# Sunfish_ECU_CPU_RevA.net
KiCad netlist of a schematic drawn in Altium Designer
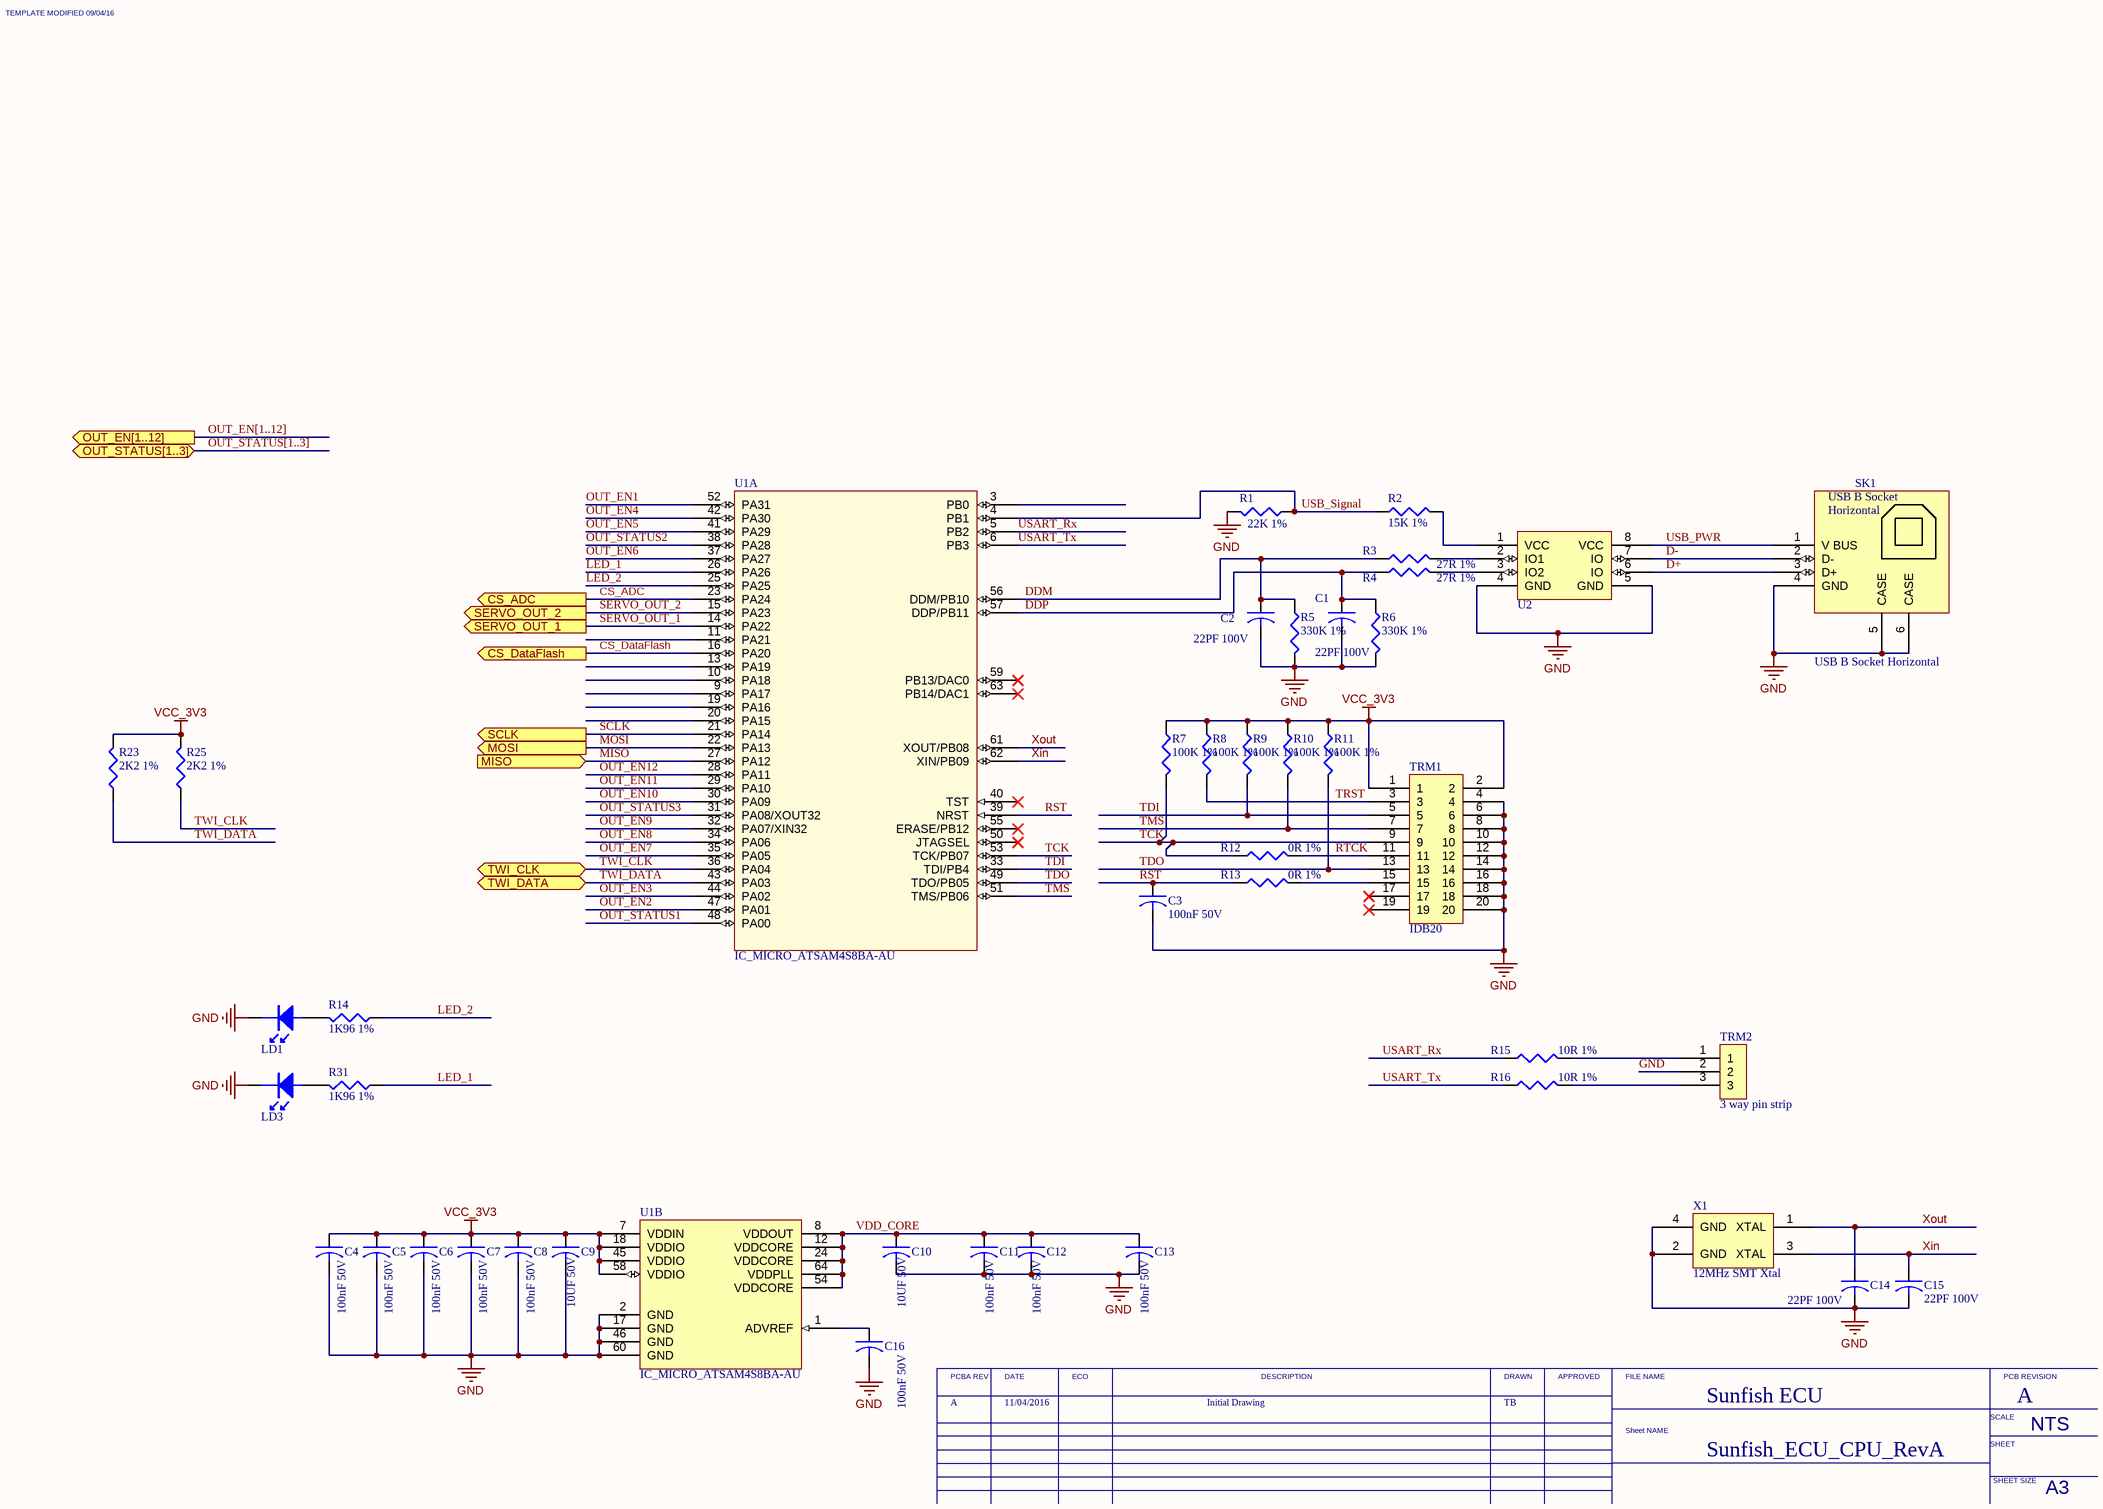
[diagram p0: Sunfish_ECU_CPU_RevA.SchDoc]

(export (version "E")
  (design (tool "Eeschema 10.0.6"))
  (components
    (comp (ref "C1")
      (value "22PF 100V")
      (footprint "0603")
      (description "CAP CER 22PF 100V 5% NP0 0603")
      (fields (field (name "MANUFACTURER") "Murata"))
      (libsource (lib "") (part "CAP_22PF_100V_5%_0603_1"))
    )
    (comp (ref "C2")
      (value "22PF 100V")
      (footprint "0603")
      (description "CAP CER 22PF 100V 5% NP0 0603")
      (fields (field (name "MANUFACTURER") "Murata"))
      (libsource (lib "") (part "CAP_22PF_100V_5%_0603_1"))
    )
    (comp (ref "C3")
      (value "100nF 50V")
      (footprint "0603")
      (description "CAP CER 100nF 50V 10% X7R 0603")
      (fields (field (name "MANUFACTURER") "Murata"))
      (libsource (lib "ThrusterControl") (part "CAP_100NF_50V_10%_0603"))
    )
    (comp (ref "C4")
      (value "100nF 50V")
      (footprint "0603")
      (description "CAP CER 100nF 50V 10% X7R 0603")
      (fields (field (name "MANUFACTURER") "Murata"))
      (libsource (lib "Caps") (part "CAP_100NF_50V_10%_0603"))
    )
    (comp (ref "C5")
      (value "100nF 50V")
      (footprint "0603")
      (description "CAP CER 100nF 50V 10% X7R 0603")
      (fields (field (name "MANUFACTURER") "Murata"))
      (libsource (lib "Caps") (part "CAP_100NF_50V_10%_0603"))
    )
    (comp (ref "C6")
      (value "100nF 50V")
      (footprint "0603")
      (description "CAP CER 100nF 50V 10% X7R 0603")
      (fields (field (name "MANUFACTURER") "Murata"))
      (libsource (lib "Caps") (part "CAP_100NF_50V_10%_0603"))
    )
    (comp (ref "C7")
      (value "100nF 50V")
      (footprint "0603")
      (description "CAP CER 100nF 50V 10% X7R 0603")
      (fields (field (name "MANUFACTURER") "Murata"))
      (libsource (lib "Caps") (part "CAP_100NF_50V_10%_0603"))
    )
    (comp (ref "C8")
      (value "100nF 50V")
      (footprint "0603")
      (description "CAP CER 100nF 50V 10% X7R 0603")
      (fields (field (name "MANUFACTURER") "Murata"))
      (libsource (lib "Caps") (part "CAP_100NF_50V_10%_0603"))
    )
    (comp (ref "C9")
      (value "10UF 50V")
      (footprint "1206")
      (description "CAP CER 10UF 50V 10% X5R 1206")
      (fields (field (name "MANUFACTURER") "Murata"))
      (libsource (lib "ThrusterControl") (part "CAP_10UF_50V_10%_1206"))
    )
    (comp (ref "C10")
      (value "10UF 50V")
      (footprint "1206")
      (description "CAP CER 10UF 50V 10% X5R 1206")
      (fields (field (name "MANUFACTURER") "Murata"))
      (libsource (lib "ThrusterControl") (part "CAP_10UF_50V_10%_1206"))
    )
    (comp (ref "C11")
      (value "100nF 50V")
      (footprint "0603")
      (description "CAP CER 100nF 50V 10% X7R 0603")
      (fields (field (name "MANUFACTURER") "Murata"))
      (libsource (lib "") (part "CAP_100NF_50V_10%_0603_1"))
    )
    (comp (ref "C12")
      (value "100nF 50V")
      (footprint "0603")
      (description "CAP CER 100nF 50V 10% X7R 0603")
      (fields (field (name "MANUFACTURER") "Murata"))
      (libsource (lib "") (part "CAP_100NF_50V_10%_0603_1"))
    )
    (comp (ref "C13")
      (value "100nF 50V")
      (footprint "0603")
      (description "CAP CER 100nF 50V 10% X7R 0603")
      (fields (field (name "MANUFACTURER") "Murata"))
      (libsource (lib "") (part "CAP_100NF_50V_10%_0603_1"))
    )
    (comp (ref "C14")
      (value "22PF 100V")
      (footprint "0603")
      (description "CAP CER 22PF 100V 5% NP0 0603")
      (fields (field (name "MANUFACTURER") "Murata"))
      (libsource (lib "ThrusterControl") (part "CAP_22PF_100V_5%_0603"))
    )
    (comp (ref "C15")
      (value "22PF 100V")
      (footprint "0603")
      (description "CAP CER 22PF 100V 5% NP0 0603")
      (fields (field (name "MANUFACTURER") "Murata"))
      (libsource (lib "ThrusterControl") (part "CAP_22PF_100V_5%_0603"))
    )
    (comp (ref "C16")
      (value "100nF 50V")
      (footprint "0603")
      (description "CAP CER 100nF 50V 10% X7R 0603")
      (fields (field (name "MANUFACTURER") "Murata"))
      (libsource (lib "") (part "CAP_100NF_50V_10%_0603_1"))
    )
    (comp (ref "LD1")
      (value "Green LED 0805")
      (footprint "0805DIODE")
      (description "WL-SMCW SMD CHIP LED WATERCLEAR")
      (fields (field (name "MANUFACTURER") "Wurth"))
      (libsource (lib "Semiconductors") (part "LED_Green_0805"))
    )
    (comp (ref "LD3")
      (value "Green LED 0805")
      (footprint "0805DIODE")
      (description "WL-SMCW SMD CHIP LED WATERCLEAR")
      (fields (field (name "MANUFACTURER") "Wurth"))
      (libsource (lib "Semiconductors") (part "LED_Green_0805"))
    )
    (comp (ref "R1")
      (value "22K 1%")
      (footprint "0603")
      (description "Resistor, 22K, 1%, 0603")
      (fields (field (name "MANUFACTURER") "Bourns Inc"))
      (libsource (lib "ThrusterControl") (part "RES_22K_1%_0603"))
    )
    (comp (ref "R2")
      (value "15K 1%")
      (footprint "0603")
      (description "Resistor, 15K, 1%, 0603")
      (fields (field (name "MANUFACTURER") "Bourns Inc"))
      (libsource (lib "ThrusterControl") (part "RES_15K_1%_0603"))
    )
    (comp (ref "R3")
      (value "27R 1%")
      (footprint "0603")
      (description "Resistor, 27R, 1%, 0603")
      (fields (field (name "MANUFACTURER") "Bourns Inc"))
      (libsource (lib "ThrusterControl") (part "RES_27R_1%_0603"))
    )
    (comp (ref "R4")
      (value "27R 1%")
      (footprint "0603")
      (description "Resistor, 27R, 1%, 0603")
      (fields (field (name "MANUFACTURER") "Bourns Inc"))
      (libsource (lib "ThrusterControl") (part "RES_27R_1%_0603"))
    )
    (comp (ref "R5")
      (value "330K 1%")
      (footprint "0603")
      (description "Resistor, 330K, 1%, 0603")
      (fields (field (name "MANUFACTURER") "Bourns Inc"))
      (libsource (lib "Resistors") (part "RES_330K_1%_0603"))
    )
    (comp (ref "R6")
      (value "330K 1%")
      (footprint "0603")
      (description "Resistor, 330K, 1%, 0603")
      (fields (field (name "MANUFACTURER") "Bourns Inc"))
      (libsource (lib "Resistors") (part "RES_330K_1%_0603"))
    )
    (comp (ref "R7")
      (value "100K 1%")
      (footprint "0603")
      (description "Resistor, 100K, 1%, 0603")
      (fields (field (name "MANUFACTURER") "Bourns Inc"))
      (libsource (lib "ThrusterControl") (part "RES_100K_1%_0603"))
    )
    (comp (ref "R8")
      (value "100K 1%")
      (footprint "0603")
      (description "Resistor, 100K, 1%, 0603")
      (fields (field (name "MANUFACTURER") "Bourns Inc"))
      (libsource (lib "ThrusterControl") (part "RES_100K_1%_0603"))
    )
    (comp (ref "R9")
      (value "100K 1%")
      (footprint "0603")
      (description "Resistor, 100K, 1%, 0603")
      (fields (field (name "MANUFACTURER") "Bourns Inc"))
      (libsource (lib "ThrusterControl") (part "RES_100K_1%_0603"))
    )
    (comp (ref "R10")
      (value "100K 1%")
      (footprint "0603")
      (description "Resistor, 100K, 1%, 0603")
      (fields (field (name "MANUFACTURER") "Bourns Inc"))
      (libsource (lib "ThrusterControl") (part "RES_100K_1%_0603"))
    )
    (comp (ref "R11")
      (value "100K 1%")
      (footprint "0603")
      (description "Resistor, 100K, 1%, 0603")
      (fields (field (name "MANUFACTURER") "Bourns Inc"))
      (libsource (lib "ThrusterControl") (part "RES_100K_1%_0603"))
    )
    (comp (ref "R12")
      (value "0R 1%")
      (footprint "0603")
      (description "Resistor, 0R, 1%, 0603")
      (fields (field (name "MANUFACTURER") "Bourns Inc"))
      (libsource (lib "ThrusterControl") (part "RES_0R_1%_0603"))
    )
    (comp (ref "R13")
      (value "0R 1%")
      (footprint "0603")
      (description "Resistor, 0R, 1%, 0603")
      (fields (field (name "MANUFACTURER") "Bourns Inc"))
      (libsource (lib "ThrusterControl") (part "RES_0R_1%_0603"))
    )
    (comp (ref "R14")
      (value "1K96 1%")
      (footprint "0603")
      (description "Resistor, 1K96, 1%, 0603")
      (fields (field (name "MANUFACTURER") "Yageo"))
      (libsource (lib "Resistors") (part "RES_1K96_1%_0603"))
    )
    (comp (ref "R15")
      (value "10R 1%")
      (footprint "0603")
      (description "Resistor, 10R, 1%, 0603")
      (fields (field (name "MANUFACTURER") "Bourns Inc"))
      (libsource (lib "ThrusterControl") (part "RES_10R_1%_0603"))
    )
    (comp (ref "R16")
      (value "10R 1%")
      (footprint "0603")
      (description "Resistor, 10R, 1%, 0603")
      (fields (field (name "MANUFACTURER") "Bourns Inc"))
      (libsource (lib "ThrusterControl") (part "RES_10R_1%_0603"))
    )
    (comp (ref "R23")
      (value "2K2 1%")
      (footprint "0603")
      (description "Resistor, 2K2, 1%, 0603")
      (fields (field (name "MANUFACTURER") "Bourns Inc"))
      (libsource (lib "Resistors") (part "RES_2K2_1%_0603"))
    )
    (comp (ref "R25")
      (value "2K2 1%")
      (footprint "0603")
      (description "Resistor, 2K2, 1%, 0603")
      (fields (field (name "MANUFACTURER") "Bourns Inc"))
      (libsource (lib "Resistors") (part "RES_2K2_1%_0603"))
    )
    (comp (ref "R31")
      (value "1K96 1%")
      (footprint "0603")
      (description "Resistor, 1K96, 1%, 0603")
      (fields (field (name "MANUFACTURER") "Yageo"))
      (libsource (lib "Resistors") (part "RES_1K96_1%_0603"))
    )
    (comp (ref "SK1")
      (value "USB B Socket Horizontal")
      (footprint "USB_B_Horizontal")
      (fields (field (name "MANUFACTURER") "Wurth Electronics Inc"))
      (libsource (lib "Hardware") (part "USB_B_Horizontal"))
    )
    (comp (ref "TRM1")
      (value "IDB20")
      (footprint "IDC20_BOXED")
      (description "IDC BOX HEADER .100\" 20POS")
      (fields (field (name "MANUFACTURER") "CNC Tech"))
      (libsource (lib "Hardware") (part "TRM_IDC20"))
    )
    (comp (ref "TRM2")
      (value "3 way pin strip")
      (footprint "SIP_3")
      (description "3 Way pin strip")
      (libsource (lib "ThrusterControl") (part "TRM_3WaySocket"))
    )
    (comp (ref "U1")
      (value "IC_MICRO_ATSAM4S8BA-AU")
      (footprint "TSQFP50P1200X1200X160-64M")
      (description "64 Pin, 512KB Flash, 128K SRAM")
      (fields (field (name "MANUFACTURER") "Atmel"))
      (libsource (lib "IC") (part "IC_MICRO_ATSAM4S8BA-AU"))
    )
    (comp (ref "U2")
      (value "IC_USB_Transorb")
      (footprint "SO-8")
      (description "TVS DIODE 5.25VWM 8SOIC")
      (fields (field (name "MANUFACTURER") "STMicroelectronics"))
      (libsource (lib "IC") (part "IC_USB_Transorb"))
    )
    (comp (ref "X1")
      (value "12MHz SMT Xtal")
      (footprint "XTAL_5X3.2_SMD")
      (description "Crystal 12.0000MHz 30ppm 12pF 40 Ohm -20°C - 70°C Surface Mount 4-SMD, No Lead (DFN, LCC)")
      (fields (field (name "MANUFACTURER") "TXC CORPORATION"))
      (libsource (lib "ThrusterControl") (part "XTAL_12MHZ_SMT"))
    )
  )
  (nets
    (net (code "1") (name "/CS_ADC") (class "Default")
      (node (ref "U1") (pin "23") (pinfunction "PA24_23") (pintype "bidirectional"))
    )
    (net (code "2") (name "/CS_DataFlash") (class "Default")
      (node (ref "U1") (pin "16") (pinfunction "PA20_16") (pintype "bidirectional"))
    )
    (net (code "3") (name "/D+") (class "Default")
      (node (ref "SK1") (pin "3") (pinfunction "D+_3") (pintype "bidirectional"))
      (node (ref "U2") (pin "6") (pinfunction "IO_6") (pintype "bidirectional"))
    )
    (net (code "4") (name "/D-") (class "Default")
      (node (ref "SK1") (pin "2") (pinfunction "D-_2") (pintype "bidirectional"))
      (node (ref "U2") (pin "7") (pinfunction "IO_7") (pintype "bidirectional"))
    )
    (net (code "5") (name "/DDM") (class "Default")
      (node (ref "C2") (pin "1") (pinfunction "1_1") (pintype "passive"))
      (node (ref "R3") (pin "2") (pintype "passive"))
      (node (ref "R5") (pin "2") (pintype "passive"))
      (node (ref "U1") (pin "56") (pinfunction "DDM/PB10_56") (pintype "bidirectional"))
    )
    (net (code "6") (name "/DDP") (class "Default")
      (node (ref "C1") (pin "1") (pinfunction "1_1") (pintype "passive"))
      (node (ref "R4") (pin "2") (pintype "passive"))
      (node (ref "R6") (pin "2") (pintype "passive"))
      (node (ref "U1") (pin "57") (pinfunction "DDP/PB11_57") (pintype "bidirectional"))
    )
    (net (code "7") (name "/LED_1") (class "Default")
      (node (ref "R31") (pin "1") (pintype "passive"))
      (node (ref "U1") (pin "26") (pinfunction "PA26_26") (pintype "bidirectional"))
    )
    (net (code "8") (name "/LED_2") (class "Default")
      (node (ref "R14") (pin "1") (pintype "passive"))
      (node (ref "U1") (pin "25") (pinfunction "PA25_25") (pintype "bidirectional"))
    )
    (net (code "9") (name "/MISO") (class "Default")
      (node (ref "U1") (pin "27") (pinfunction "PA12_27") (pintype "bidirectional"))
    )
    (net (code "10") (name "/MOSI") (class "Default")
      (node (ref "U1") (pin "22") (pinfunction "PA13_22") (pintype "bidirectional"))
    )
    (net (code "11") (name "/OUT_EN1") (class "Default")
      (node (ref "U1") (pin "52") (pinfunction "PA31_52") (pintype "bidirectional"))
    )
    (net (code "12") (name "/OUT_EN2") (class "Default")
      (node (ref "U1") (pin "47") (pinfunction "PA01_47") (pintype "bidirectional"))
    )
    (net (code "13") (name "/OUT_EN3") (class "Default")
      (node (ref "U1") (pin "44") (pinfunction "PA02_44") (pintype "bidirectional"))
    )
    (net (code "14") (name "/OUT_EN4") (class "Default")
      (node (ref "U1") (pin "42") (pinfunction "PA30_42") (pintype "bidirectional"))
    )
    (net (code "15") (name "/OUT_EN5") (class "Default")
      (node (ref "U1") (pin "41") (pinfunction "PA29_41") (pintype "bidirectional"))
    )
    (net (code "16") (name "/OUT_EN6") (class "Default")
      (node (ref "U1") (pin "37") (pinfunction "PA27_37") (pintype "bidirectional"))
    )
    (net (code "17") (name "/OUT_EN7") (class "Default")
      (node (ref "U1") (pin "35") (pinfunction "PA05_35") (pintype "bidirectional"))
    )
    (net (code "18") (name "/OUT_EN8") (class "Default")
      (node (ref "U1") (pin "34") (pinfunction "PA06_34") (pintype "bidirectional"))
    )
    (net (code "19") (name "/OUT_EN9") (class "Default")
      (node (ref "U1") (pin "32") (pinfunction "PA07/XIN32_32") (pintype "bidirectional"))
    )
    (net (code "20") (name "/OUT_EN10") (class "Default")
      (node (ref "U1") (pin "30") (pinfunction "PA09_30") (pintype "bidirectional"))
    )
    (net (code "21") (name "/OUT_EN11") (class "Default")
      (node (ref "U1") (pin "29") (pinfunction "PA10_29") (pintype "bidirectional"))
    )
    (net (code "22") (name "/OUT_EN12") (class "Default")
      (node (ref "U1") (pin "28") (pinfunction "PA11_28") (pintype "bidirectional"))
    )
    (net (code "24") (name "/OUT_STATUS1") (class "Default")
      (node (ref "U1") (pin "48") (pinfunction "PA00_48") (pintype "bidirectional"))
    )
    (net (code "25") (name "/OUT_STATUS2") (class "Default")
      (node (ref "U1") (pin "38") (pinfunction "PA28_38") (pintype "bidirectional"))
    )
    (net (code "26") (name "/OUT_STATUS3") (class "Default")
      (node (ref "U1") (pin "31") (pinfunction "PA08/XOUT32_31") (pintype "bidirectional"))
    )
    (net (code "28") (name "/RST") (class "Default")
      (node (ref "C3") (pin "1") (pinfunction "1_1") (pintype "passive"))
      (node (ref "R13") (pin "2") (pintype "passive"))
      (node (ref "U1") (pin "39") (pinfunction "NRST_39") (pintype "input"))
    )
    (net (code "29") (name "/RTCK") (class "Default")
      (node (ref "R12") (pin "1") (pintype "passive"))
      (node (ref "TRM1") (pin "11") (pinfunction "11_11") (pintype "power_in"))
    )
    (net (code "30") (name "/SCLK") (class "Default")
      (node (ref "U1") (pin "21") (pinfunction "PA14_21") (pintype "bidirectional"))
    )
    (net (code "31") (name "/SERVO_OUT_1") (class "Default")
      (node (ref "U1") (pin "14") (pinfunction "PA22_14") (pintype "bidirectional"))
    )
    (net (code "32") (name "/SERVO_OUT_2") (class "Default")
      (node (ref "U1") (pin "15") (pinfunction "PA23_15") (pintype "bidirectional"))
    )
    (net (code "33") (name "/TCK") (class "Default")
      (node (ref "R12") (pin "2") (pintype "passive"))
      (node (ref "R7") (pin "1") (pintype "passive"))
      (node (ref "TRM1") (pin "9") (pinfunction "9_9") (pintype "power_in"))
      (node (ref "U1") (pin "53") (pinfunction "TCK/PB07_53") (pintype "bidirectional"))
    )
    (net (code "34") (name "/TDI") (class "Default")
      (node (ref "R9") (pin "1") (pintype "passive"))
      (node (ref "TRM1") (pin "5") (pinfunction "5_5") (pintype "power_in"))
      (node (ref "U1") (pin "33") (pinfunction "TDI/PB4_33") (pintype "bidirectional"))
    )
    (net (code "35") (name "/TDO") (class "Default")
      (node (ref "R11") (pin "1") (pintype "passive"))
      (node (ref "TRM1") (pin "13") (pinfunction "13_13") (pintype "power_in"))
      (node (ref "U1") (pin "49") (pinfunction "TDO/PB05_49") (pintype "bidirectional"))
    )
    (net (code "36") (name "/TMS") (class "Default")
      (node (ref "R10") (pin "1") (pintype "passive"))
      (node (ref "TRM1") (pin "7") (pinfunction "7_7") (pintype "power_in"))
      (node (ref "U1") (pin "51") (pinfunction "TMS/PB06_51") (pintype "bidirectional"))
    )
    (net (code "37") (name "/TRST") (class "Default")
      (node (ref "R8") (pin "1") (pintype "passive"))
      (node (ref "TRM1") (pin "3") (pinfunction "3_3") (pintype "power_in"))
    )
    (net (code "38") (name "/TWI_CLK") (class "Default")
      (node (ref "R25") (pin "1") (pintype "passive"))
      (node (ref "U1") (pin "36") (pinfunction "PA04_36") (pintype "bidirectional"))
    )
    (net (code "39") (name "/TWI_DATA") (class "Default")
      (node (ref "R23") (pin "1") (pintype "passive"))
      (node (ref "U1") (pin "43") (pinfunction "PA03_43") (pintype "bidirectional"))
    )
    (net (code "40") (name "/USART_Rx") (class "Default")
      (node (ref "R15") (pin "1") (pintype "passive"))
      (node (ref "U1") (pin "5") (pinfunction "PB2_5") (pintype "bidirectional"))
    )
    (net (code "41") (name "/USART_Tx") (class "Default")
      (node (ref "R16") (pin "1") (pintype "passive"))
      (node (ref "U1") (pin "6") (pinfunction "PB3_6") (pintype "bidirectional"))
    )
    (net (code "42") (name "/USB_PWR") (class "Default")
      (node (ref "SK1") (pin "1") (pinfunction "V_BUS_1") (pintype "power_in"))
      (node (ref "U2") (pin "8") (pinfunction "VCC_8") (pintype "power_in"))
    )
    (net (code "43") (name "/USB_Signal") (class "Default")
      (node (ref "R1") (pin "2") (pintype "passive"))
      (node (ref "R2") (pin "2") (pintype "passive"))
      (node (ref "U1") (pin "4") (pinfunction "PB1_4") (pintype "bidirectional"))
    )
    (net (code "44") (name "/VDD_CORE") (class "Default")
      (node (ref "C10") (pin "1") (pinfunction "1_1") (pintype "passive"))
      (node (ref "C11") (pin "1") (pinfunction "1_1") (pintype "passive"))
      (node (ref "C12") (pin "1") (pinfunction "1_1") (pintype "passive"))
      (node (ref "C13") (pin "1") (pinfunction "1_1") (pintype "passive"))
      (node (ref "U1") (pin "12") (pinfunction "VDDCORE_12") (pintype "power_in"))
      (node (ref "U1") (pin "24") (pinfunction "VDDCORE_24") (pintype "power_in"))
      (node (ref "U1") (pin "54") (pinfunction "VDDCORE_54") (pintype "power_in"))
      (node (ref "U1") (pin "64") (pinfunction "VDDPLL_64") (pintype "power_in"))
      (node (ref "U1") (pin "8") (pinfunction "VDDOUT_8") (pintype "power_in"))
    )
    (net (code "45") (name "/Xin") (class "Default")
      (node (ref "C15") (pin "1") (pinfunction "1_1") (pintype "passive"))
      (node (ref "U1") (pin "62") (pinfunction "XIN/PB09_62") (pintype "bidirectional"))
      (node (ref "X1") (pin "3") (pinfunction "XTAL_3") (pintype "tri_state"))
    )
    (net (code "46") (name "/Xout") (class "Default")
      (node (ref "C14") (pin "1") (pinfunction "1_1") (pintype "passive"))
      (node (ref "U1") (pin "61") (pinfunction "XOUT/PB08_61") (pintype "bidirectional"))
      (node (ref "X1") (pin "1") (pinfunction "XTAL_1") (pintype "tri_state"))
    )
    (net (code "47") (name "GND") (class "Default")
      (node (ref "C1") (pin "2") (pinfunction "2_2") (pintype "passive"))
      (node (ref "C10") (pin "2") (pinfunction "2_2") (pintype "passive"))
      (node (ref "C11") (pin "2") (pinfunction "2_2") (pintype "passive"))
      (node (ref "C12") (pin "2") (pinfunction "2_2") (pintype "passive"))
      (node (ref "C13") (pin "2") (pinfunction "2_2") (pintype "passive"))
      (node (ref "C14") (pin "2") (pinfunction "2_2") (pintype "passive"))
      (node (ref "C15") (pin "2") (pinfunction "2_2") (pintype "passive"))
      (node (ref "C16") (pin "2") (pinfunction "2_2") (pintype "passive"))
      (node (ref "C2") (pin "2") (pinfunction "2_2") (pintype "passive"))
      (node (ref "C3") (pin "2") (pinfunction "2_2") (pintype "passive"))
      (node (ref "C4") (pin "2") (pinfunction "2_2") (pintype "passive"))
      (node (ref "C5") (pin "2") (pinfunction "2_2") (pintype "passive"))
      (node (ref "C6") (pin "2") (pinfunction "2_2") (pintype "passive"))
      (node (ref "C7") (pin "2") (pinfunction "2_2") (pintype "passive"))
      (node (ref "C8") (pin "2") (pinfunction "2_2") (pintype "passive"))
      (node (ref "C9") (pin "2") (pinfunction "2_2") (pintype "passive"))
      (node (ref "LD1") (pin "K") (pintype "passive"))
      (node (ref "LD3") (pin "K") (pintype "passive"))
      (node (ref "R1") (pin "1") (pintype "passive"))
      (node (ref "R5") (pin "1") (pintype "passive"))
      (node (ref "R6") (pin "1") (pintype "passive"))
      (node (ref "SK1") (pin "4") (pinfunction "GND_4") (pintype "power_in"))
      (node (ref "SK1") (pin "5") (pinfunction "CASE_5") (pintype "power_in"))
      (node (ref "SK1") (pin "6") (pinfunction "CASE_6") (pintype "power_in"))
      (node (ref "TRM1") (pin "10") (pinfunction "10_10") (pintype "power_in"))
      (node (ref "TRM1") (pin "12") (pinfunction "12_12") (pintype "power_in"))
      (node (ref "TRM1") (pin "14") (pinfunction "14_14") (pintype "power_in"))
      (node (ref "TRM1") (pin "16") (pinfunction "16_16") (pintype "power_in"))
      (node (ref "TRM1") (pin "18") (pinfunction "18_18") (pintype "power_in"))
      (node (ref "TRM1") (pin "20") (pinfunction "20_20") (pintype "power_in"))
      (node (ref "TRM1") (pin "4") (pinfunction "4_4") (pintype "power_in"))
      (node (ref "TRM1") (pin "6") (pinfunction "6_6") (pintype "power_in"))
      (node (ref "TRM1") (pin "8") (pinfunction "8_8") (pintype "power_in"))
      (node (ref "TRM2") (pin "2") (pinfunction "2_2") (pintype "tri_state"))
      (node (ref "U1") (pin "17") (pinfunction "GND_17") (pintype "power_in"))
      (node (ref "U1") (pin "2") (pinfunction "GND_2") (pintype "power_in"))
      (node (ref "U1") (pin "46") (pinfunction "GND_46") (pintype "power_in"))
      (node (ref "U1") (pin "60") (pinfunction "GND_60") (pintype "power_in"))
      (node (ref "U2") (pin "4") (pinfunction "GND_4") (pintype "power_in"))
      (node (ref "U2") (pin "5") (pinfunction "GND_5") (pintype "power_in"))
      (node (ref "X1") (pin "2") (pinfunction "GND_2") (pintype "tri_state"))
      (node (ref "X1") (pin "4") (pinfunction "GND_4") (pintype "tri_state"))
    )
    (net (code "48") (name "Net-(LD1-PadA)") (class "Default")
      (node (ref "LD1") (pin "A") (pintype "passive"))
      (node (ref "R14") (pin "2") (pintype "passive"))
    )
    (net (code "49") (name "Net-(LD3-PadA)") (class "Default")
      (node (ref "LD3") (pin "A") (pintype "passive"))
      (node (ref "R31") (pin "2") (pintype "passive"))
    )
    (net (code "50") (name "Net-(R2-Pad1)") (class "Default")
      (node (ref "R2") (pin "1") (pintype "passive"))
      (node (ref "U2") (pin "1") (pinfunction "VCC_1") (pintype "power_in"))
    )
    (net (code "51") (name "Net-(R13-Pad1)") (class "Default")
      (node (ref "R13") (pin "1") (pintype "passive"))
      (node (ref "TRM1") (pin "15") (pinfunction "15_15") (pintype "power_in"))
    )
    (net (code "52") (name "Net-(R15-Pad2)") (class "Default")
      (node (ref "R15") (pin "2") (pintype "passive"))
      (node (ref "TRM2") (pin "1") (pinfunction "1_1") (pintype "tri_state"))
    )
    (net (code "53") (name "Net-(R16-Pad2)") (class "Default")
      (node (ref "R16") (pin "2") (pintype "passive"))
      (node (ref "TRM2") (pin "3") (pinfunction "3_3") (pintype "tri_state"))
    )
    (net (code "54") (name "Net-(U1B-ADVREF)") (class "Default")
      (node (ref "C16") (pin "1") (pinfunction "1_1") (pintype "passive"))
      (node (ref "U1") (pin "1") (pinfunction "ADVREF_1") (pintype "input"))
    )
    (net (code "55") (name "Net-(U2-IO1)") (class "Default")
      (node (ref "R3") (pin "1") (pintype "passive"))
      (node (ref "U2") (pin "2") (pinfunction "IO1_2") (pintype "bidirectional"))
    )
    (net (code "56") (name "Net-(U2-IO2)") (class "Default")
      (node (ref "R4") (pin "1") (pintype "passive"))
      (node (ref "U2") (pin "3") (pinfunction "IO2_3") (pintype "bidirectional"))
    )
    (net (code "57") (name "VCC_3V3") (class "Default")
      (node (ref "C4") (pin "1") (pinfunction "1_1") (pintype "passive"))
      (node (ref "C5") (pin "1") (pinfunction "1_1") (pintype "passive"))
      (node (ref "C6") (pin "1") (pinfunction "1_1") (pintype "passive"))
      (node (ref "C7") (pin "1") (pinfunction "1_1") (pintype "passive"))
      (node (ref "C8") (pin "1") (pinfunction "1_1") (pintype "passive"))
      (node (ref "C9") (pin "1") (pinfunction "1_1") (pintype "passive"))
      (node (ref "R10") (pin "2") (pintype "passive"))
      (node (ref "R11") (pin "2") (pintype "passive"))
      (node (ref "R23") (pin "2") (pintype "passive"))
      (node (ref "R25") (pin "2") (pintype "passive"))
      (node (ref "R7") (pin "2") (pintype "passive"))
      (node (ref "R8") (pin "2") (pintype "passive"))
      (node (ref "R9") (pin "2") (pintype "passive"))
      (node (ref "TRM1") (pin "1") (pinfunction "1_1") (pintype "power_in"))
      (node (ref "TRM1") (pin "2") (pinfunction "2_2") (pintype "power_in"))
      (node (ref "U1") (pin "18") (pinfunction "VDDIO_18") (pintype "power_in"))
      (node (ref "U1") (pin "45") (pinfunction "VDDIO_45") (pintype "power_in"))
      (node (ref "U1") (pin "58") (pinfunction "VDDIO_58") (pintype "bidirectional"))
      (node (ref "U1") (pin "7") (pinfunction "VDDIN_7") (pintype "power_in"))
    )
    (net (code "58") (name "unconnected-(TRM1-Pad17)") (class "Default")
      (node (ref "TRM1") (pin "17") (pinfunction "17_17") (pintype "power_in+no_connect"))
    )
    (net (code "59") (name "unconnected-(TRM1-Pad19)") (class "Default")
      (node (ref "TRM1") (pin "19") (pinfunction "19_19") (pintype "power_in+no_connect"))
    )
    (net (code "60") (name "unconnected-(U1A-ERASE{slash}PB12-Pad55)") (class "Default")
      (node (ref "U1") (pin "55") (pinfunction "ERASE/PB12_55") (pintype "bidirectional+no_connect"))
    )
    (net (code "61") (name "unconnected-(U1A-JTAGSEL-Pad50)") (class "Default")
      (node (ref "U1") (pin "50") (pinfunction "JTAGSEL_50") (pintype "bidirectional+no_connect"))
    )
    (net (code "62") (name "unconnected-(U1A-PA15-Pad20)") (class "Default")
      (node (ref "U1") (pin "20") (pinfunction "PA15_20") (pintype "bidirectional"))
    )
    (net (code "63") (name "unconnected-(U1A-PA16-Pad19)") (class "Default")
      (node (ref "U1") (pin "19") (pinfunction "PA16_19") (pintype "bidirectional"))
    )
    (net (code "64") (name "unconnected-(U1A-PA17-Pad9)") (class "Default")
      (node (ref "U1") (pin "9") (pinfunction "PA17_9") (pintype "bidirectional"))
    )
    (net (code "65") (name "unconnected-(U1A-PA18-Pad10)") (class "Default")
      (node (ref "U1") (pin "10") (pinfunction "PA18_10") (pintype "bidirectional"))
    )
    (net (code "66") (name "unconnected-(U1A-PA19-Pad13)") (class "Default")
      (node (ref "U1") (pin "13") (pinfunction "PA19_13") (pintype "bidirectional"))
    )
    (net (code "67") (name "unconnected-(U1A-PA21-Pad11)") (class "Default")
      (node (ref "U1") (pin "11") (pinfunction "PA21_11") (pintype "bidirectional"))
    )
    (net (code "68") (name "unconnected-(U1A-PB0-Pad3)") (class "Default")
      (node (ref "U1") (pin "3") (pinfunction "PB0_3") (pintype "bidirectional"))
    )
    (net (code "69") (name "unconnected-(U1A-PB13{slash}DAC0-Pad59)") (class "Default")
      (node (ref "U1") (pin "59") (pinfunction "PB13/DAC0_59") (pintype "bidirectional+no_connect"))
    )
    (net (code "70") (name "unconnected-(U1A-PB14{slash}DAC1-Pad63)") (class "Default")
      (node (ref "U1") (pin "63") (pinfunction "PB14/DAC1_63") (pintype "bidirectional+no_connect"))
    )
    (net (code "71") (name "unconnected-(U1A-TST-Pad40)") (class "Default")
      (node (ref "U1") (pin "40") (pinfunction "TST_40") (pintype "input+no_connect"))
    )
  )
)
